# EEGAmp_SMT.net
KiCad netlist of a schematic drawn in EAGLE
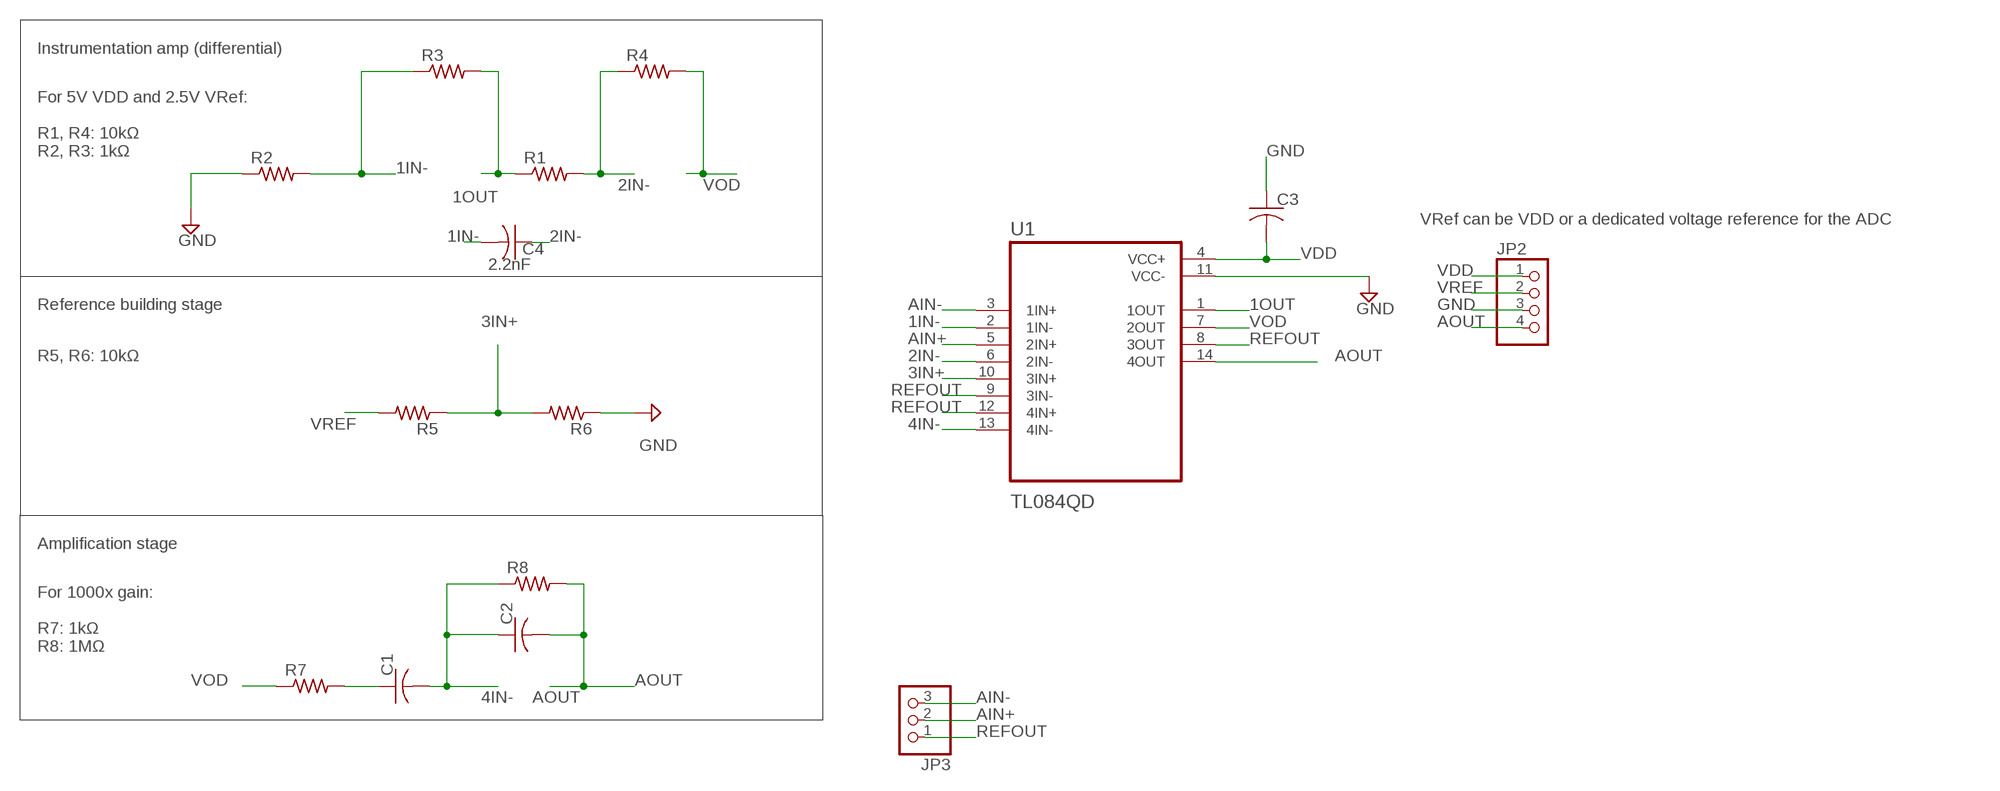
[diagram p0: schematic, sheet 1]

(export (version "E")
  (design (tool "Eeschema 10.0.6"))
  (components
    (comp (ref "C1")
      (value "C-USC0402")
      (footprint "eagle-import:C0402")
      (libsource (lib "eagle-import") (part "C-USC0402"))
    )
    (comp (ref "C2")
      (value "C-USC0402")
      (footprint "eagle-import:C0402")
      (libsource (lib "eagle-import") (part "C-USC0402"))
    )
    (comp (ref "C3")
      (value "C-USC0402")
      (footprint "eagle-import:C0402")
      (libsource (lib "eagle-import") (part "C-USC0402"))
    )
    (comp (ref "C4")
      (value "2.2nF")
      (footprint "eagle-import:C0402")
      (libsource (lib "eagle-import") (part "C-USC0402"))
    )
    (comp (ref "JP2")
      (value "PINHD-1X4")
      (footprint "eagle-import:1X04")
      (libsource (lib "eagle-import") (part "PINHD-1X4"))
    )
    (comp (ref "JP3")
      (value "PINHD-1X3")
      (footprint "eagle-import:1X03")
      (libsource (lib "eagle-import") (part "PINHD-1X3"))
    )
    (comp (ref "R1")
      (value "R-US_R0402")
      (footprint "eagle-import:R0402")
      (libsource (lib "eagle-import") (part "R-US_R0402"))
    )
    (comp (ref "R2")
      (value "R-US_R0402")
      (footprint "eagle-import:R0402")
      (libsource (lib "eagle-import") (part "R-US_R0402"))
    )
    (comp (ref "R3")
      (value "R-US_R0402")
      (footprint "eagle-import:R0402")
      (libsource (lib "eagle-import") (part "R-US_R0402"))
    )
    (comp (ref "R4")
      (value "R-US_R0402")
      (footprint "eagle-import:R0402")
      (libsource (lib "eagle-import") (part "R-US_R0402"))
    )
    (comp (ref "R5")
      (value "R-US_R0402")
      (footprint "eagle-import:R0402")
      (libsource (lib "eagle-import") (part "R-US_R0402"))
    )
    (comp (ref "R6")
      (value "R-US_R0402")
      (footprint "eagle-import:R0402")
      (libsource (lib "eagle-import") (part "R-US_R0402"))
    )
    (comp (ref "R7")
      (value "R-US_R0402")
      (footprint "eagle-import:R0402")
      (libsource (lib "eagle-import") (part "R-US_R0402"))
    )
    (comp (ref "R8")
      (value "R-US_R0402")
      (footprint "eagle-import:R0402")
      (libsource (lib "eagle-import") (part "R-US_R0402"))
    )
    (comp (ref "U1")
      (value "TL084QD")
      (footprint "eagle-import:SOIC127P600X175-14N")
      (fields (field (name "MF") "Texas Instruments"))
      (libsource (lib "eagle-import") (part "TL084QD"))
    )
  )
  (nets
    (net (code "1") (name "/1IN-") (class "Default")
      (node (ref "C4") (pin "2") (pinfunction "2_2") (pintype "passive"))
      (node (ref "R2") (pin "2") (pinfunction "2_2") (pintype "passive"))
      (node (ref "R3") (pin "1") (pinfunction "1_1") (pintype "passive"))
      (node (ref "U1") (pin "2") (pinfunction "1IN-_2") (pintype "input"))
    )
    (net (code "2") (name "/1OUT") (class "Default")
      (node (ref "R1") (pin "1") (pinfunction "1_1") (pintype "passive"))
      (node (ref "R3") (pin "2") (pinfunction "2_2") (pintype "passive"))
      (node (ref "U1") (pin "1") (pinfunction "1OUT_1") (pintype "output"))
    )
    (net (code "3") (name "/2IN-") (class "Default")
      (node (ref "C4") (pin "1") (pinfunction "1_1") (pintype "passive"))
      (node (ref "R1") (pin "2") (pinfunction "2_2") (pintype "passive"))
      (node (ref "R4") (pin "1") (pinfunction "1_1") (pintype "passive"))
      (node (ref "U1") (pin "6") (pinfunction "2IN-_6") (pintype "input"))
    )
    (net (code "4") (name "/3IN+") (class "Default")
      (node (ref "R5") (pin "1") (pinfunction "1_1") (pintype "passive"))
      (node (ref "R6") (pin "2") (pinfunction "2_2") (pintype "passive"))
      (node (ref "U1") (pin "10") (pinfunction "3IN+_10") (pintype "input"))
    )
    (net (code "5") (name "/4IN-") (class "Default")
      (node (ref "C1") (pin "2") (pinfunction "2_2") (pintype "passive"))
      (node (ref "C2") (pin "1") (pinfunction "1_1") (pintype "passive"))
      (node (ref "R8") (pin "1") (pinfunction "1_1") (pintype "passive"))
      (node (ref "U1") (pin "13") (pinfunction "4IN-_13") (pintype "input"))
    )
    (net (code "6") (name "/AIN+") (class "Default")
      (node (ref "JP3") (pin "2") (pinfunction "2_2") (pintype "passive"))
      (node (ref "U1") (pin "5") (pinfunction "2IN+_5") (pintype "input"))
    )
    (net (code "7") (name "/AIN-") (class "Default")
      (node (ref "JP3") (pin "3") (pinfunction "3_3") (pintype "passive"))
      (node (ref "U1") (pin "3") (pinfunction "1IN+_3") (pintype "input"))
    )
    (net (code "8") (name "/AOUT") (class "Default")
      (node (ref "C2") (pin "2") (pinfunction "2_2") (pintype "passive"))
      (node (ref "JP2") (pin "4") (pinfunction "4_4") (pintype "passive"))
      (node (ref "R8") (pin "2") (pinfunction "2_2") (pintype "passive"))
      (node (ref "U1") (pin "14") (pinfunction "4OUT_14") (pintype "output"))
    )
    (net (code "9") (name "/REFOUT") (class "Default")
      (node (ref "JP3") (pin "1") (pinfunction "1_1") (pintype "passive"))
      (node (ref "U1") (pin "12") (pinfunction "4IN+_12") (pintype "input"))
      (node (ref "U1") (pin "8") (pinfunction "3OUT_8") (pintype "output"))
      (node (ref "U1") (pin "9") (pinfunction "3IN-_9") (pintype "input"))
    )
    (net (code "10") (name "/VDD") (class "Default")
      (node (ref "C3") (pin "2") (pinfunction "2_2") (pintype "passive"))
      (node (ref "JP2") (pin "1") (pinfunction "1_1") (pintype "passive"))
      (node (ref "U1") (pin "4") (pinfunction "VCC+_4") (pintype "power_in"))
    )
    (net (code "11") (name "/VOD") (class "Default")
      (node (ref "R4") (pin "2") (pinfunction "2_2") (pintype "passive"))
      (node (ref "R7") (pin "1") (pinfunction "1_1") (pintype "passive"))
      (node (ref "U1") (pin "7") (pinfunction "2OUT_7") (pintype "output"))
    )
    (net (code "12") (name "/VREF") (class "Default")
      (node (ref "JP2") (pin "2") (pinfunction "2_2") (pintype "passive"))
      (node (ref "R5") (pin "2") (pinfunction "2_2") (pintype "passive"))
    )
    (net (code "13") (name "GND") (class "Default")
      (node (ref "C3") (pin "1") (pinfunction "1_1") (pintype "passive"))
      (node (ref "JP2") (pin "3") (pinfunction "3_3") (pintype "passive"))
      (node (ref "R2") (pin "1") (pinfunction "1_1") (pintype "passive"))
      (node (ref "R6") (pin "1") (pinfunction "1_1") (pintype "passive"))
      (node (ref "U1") (pin "11") (pinfunction "VCC-_11") (pintype "power_in"))
    )
    (net (code "14") (name "Net-(C1-Pad1)") (class "Default")
      (node (ref "C1") (pin "1") (pinfunction "1_1") (pintype "passive"))
      (node (ref "R7") (pin "2") (pinfunction "2_2") (pintype "passive"))
    )
  )
)
